# MOSFETPCBSchematic.net
KiCad netlist of a schematic drawn in Altium Designer
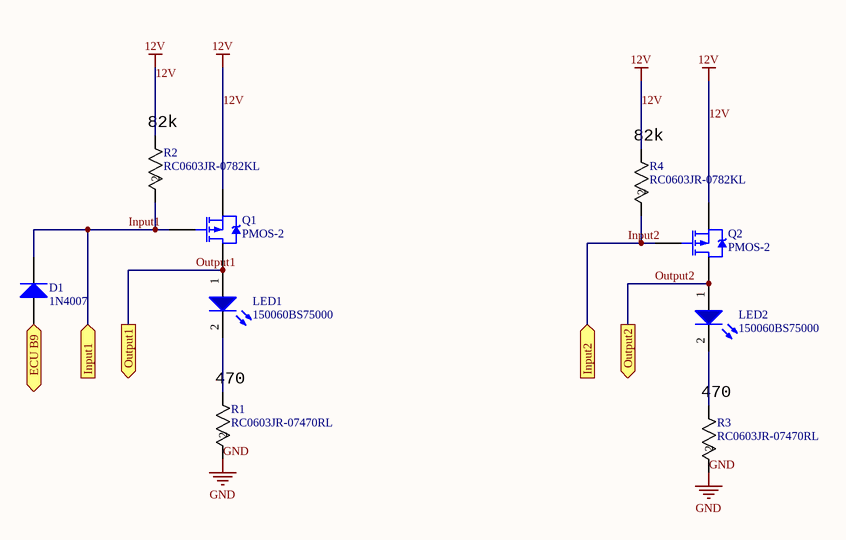
[diagram p0: MOSFETPCBSchematic.SchDoc]

(export (version "E")
  (design (tool "Eeschema 10.0.6"))
  (components
    (comp (ref "D1")
      (value "1N4007")
      (footprint "SMC")
      (description "Default Diode")
      (fields (field (name "PUBLISHER") "Altium Limited"))
      (libsource (lib "Miscellaneous Devices") (part "Diode"))
    )
    (comp (ref "LED1")
      (value "150060BS75000")
      (footprint "LED_0603_Red")
      (description "SMD mono-color Chip LED, WL-SMCW, Blue")
      (fields
        (field (name "MANUFACTURER") "W黵th Elektronik eiSos GmbH")
        (field (name "CREATED BY") "Christin Otto")
      )
      (libsource (lib "WL-SMCW_rev15b") (part "WL-SMCW 0603  150060BS75000"))
    )
    (comp (ref "LED2")
      (value "150060BS75000")
      (footprint "LED_0603_Blue")
      (description "SMD mono-color Chip LED, WL-SMCW, Blue")
      (fields
        (field (name "MANUFACTURER") "W黵th Elektronik eiSos GmbH")
        (field (name "CREATED BY") "Christin Otto")
      )
      (libsource (lib "WL-SMCW_rev15b") (part "WL-SMCW 0603  150060BS75000"))
    )
    (comp (ref "Q1")
      (value "PMOS-2")
      (footprint "SIP-G3/C6.75")
      (description "P-Channel Power MOSFET")
      (fields (field (name "PUBLISHER") "Altium Limited"))
      (libsource (lib "Miscellaneous Devices") (part "PMOS-2"))
    )
    (comp (ref "Q2")
      (value "PMOS-2")
      (footprint "SIP-G3/C6.75")
      (description "P-Channel Power MOSFET")
      (fields (field (name "PUBLISHER") "Altium Limited"))
      (libsource (lib "Miscellaneous Devices") (part "PMOS-2"))
    )
    (comp (ref "R1")
      (value "RC0603JR-07470RL")
      (footprint "RC0603N")
      (description "Imported")
      (fields
        (field (name "DIGIKEYPARTNUMBER") "311-470GRTR-ND")
        (field (name "TOLERANCE") "Â±5%")
        (field (name "ALTIUM_VALUE") "470")
        (field (name "COPYRIGHT") "Copyright (C) 2015 Accelerated Designs. All rights reserved")
      )
      (libsource (lib "Altium") (part "RC0603JR-07470RL"))
    )
    (comp (ref "R2")
      (value "RC0603JR-0782KL")
      (footprint "RC0603N")
      (description "Imported")
      (fields
        (field (name "DIGIKEYPARTNUMBER") "311-82KGRTR-ND")
        (field (name "TOLERANCE") "Â±5%")
        (field (name "ALTIUM_VALUE") "82k")
        (field (name "COPYRIGHT") "Copyright (C) 2015 Accelerated Designs. All rights reserved")
      )
      (libsource (lib "Altium82kOhm") (part "RC0603JR-0782KL"))
    )
    (comp (ref "R3")
      (value "RC0603JR-07470RL")
      (footprint "RC0603N")
      (description "Imported")
      (fields
        (field (name "DIGIKEYPARTNUMBER") "311-470GRTR-ND")
        (field (name "TOLERANCE") "Â±5%")
        (field (name "ALTIUM_VALUE") "470")
        (field (name "COPYRIGHT") "Copyright (C) 2015 Accelerated Designs. All rights reserved")
      )
      (libsource (lib "Altium") (part "RC0603JR-07470RL"))
    )
    (comp (ref "R4")
      (value "RC0603JR-0782KL")
      (footprint "RC0603N")
      (description "Imported")
      (fields
        (field (name "DIGIKEYPARTNUMBER") "311-82KGRTR-ND")
        (field (name "TOLERANCE") "Â±5%")
        (field (name "ALTIUM_VALUE") "82k")
        (field (name "COPYRIGHT") "Copyright (C) 2015 Accelerated Designs. All rights reserved")
      )
      (libsource (lib "Altium82kOhm") (part "RC0603JR-0782KL"))
    )
  )
  (nets
    (net (code "1") (name "/ECU B9") (class "Default")
      (node (ref "D1") (pin "1") (pinfunction "A_1") (pintype "passive"))
    )
    (net (code "2") (name "/Input1") (class "Default")
      (node (ref "D1") (pin "2") (pinfunction "K_2") (pintype "passive"))
      (node (ref "Q1") (pin "1") (pinfunction "G_1") (pintype "passive"))
      (node (ref "R2") (pin "2") (pinfunction "2_2") (pintype "passive"))
    )
    (net (code "3") (name "/Input2") (class "Default")
      (node (ref "Q2") (pin "1") (pinfunction "G_1") (pintype "passive"))
      (node (ref "R4") (pin "2") (pinfunction "2_2") (pintype "passive"))
    )
    (net (code "4") (name "/Output1") (class "Default")
      (node (ref "LED1") (pin "1") (pinfunction "A_1") (pintype "passive"))
      (node (ref "Q1") (pin "2") (pinfunction "D_2") (pintype "passive"))
    )
    (net (code "5") (name "/Output2") (class "Default")
      (node (ref "LED2") (pin "1") (pinfunction "A_1") (pintype "passive"))
      (node (ref "Q2") (pin "2") (pinfunction "D_2") (pintype "passive"))
    )
    (net (code "6") (name "12V") (class "Default")
      (node (ref "Q1") (pin "3") (pinfunction "S_3") (pintype "passive"))
      (node (ref "Q2") (pin "3") (pinfunction "S_3") (pintype "passive"))
      (node (ref "R2") (pin "1") (pinfunction "1_1") (pintype "passive"))
      (node (ref "R4") (pin "1") (pinfunction "1_1") (pintype "passive"))
    )
    (net (code "7") (name "GND") (class "Default")
      (node (ref "R1") (pin "2") (pinfunction "2_2") (pintype "passive"))
      (node (ref "R3") (pin "2") (pinfunction "2_2") (pintype "passive"))
    )
    (net (code "8") (name "Net-(LED1-C)") (class "Default")
      (node (ref "LED1") (pin "2") (pinfunction "C_2") (pintype "passive"))
      (node (ref "R1") (pin "1") (pinfunction "1_1") (pintype "passive"))
    )
    (net (code "9") (name "Net-(LED2-C)") (class "Default")
      (node (ref "LED2") (pin "2") (pinfunction "C_2") (pintype "passive"))
      (node (ref "R3") (pin "1") (pinfunction "1_1") (pintype "passive"))
    )
  )
)
